# I2C_switch.net
KiCad netlist of a schematic drawn in Altium Designer
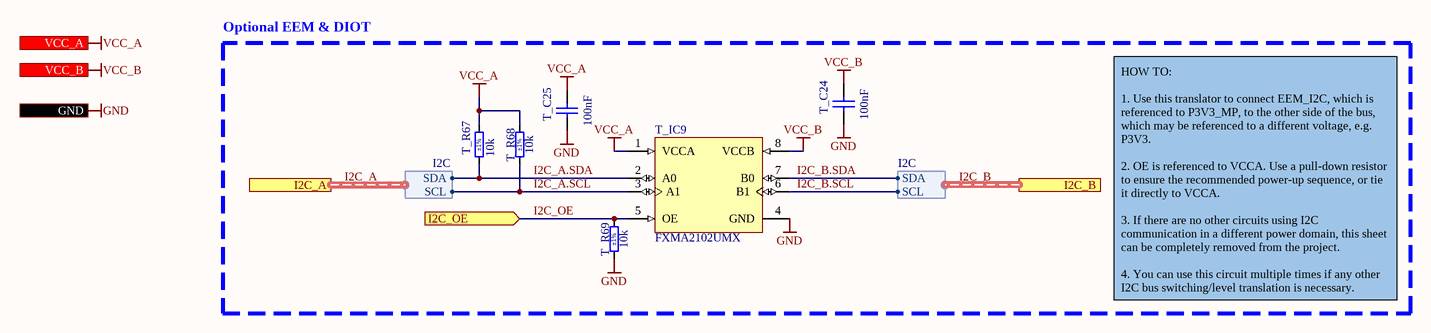
[diagram p0: I2C_switch.SchDoc]

(export (version "E")
  (design (tool "Eeschema 10.0.6"))
  (components
    (comp (ref "T_C24")
      (value "100nF")
      (footprint "CAPC1005X55N")
      (description "Non-polarised capacitor")
      (fields
        (field (name "PART NUMBER") "CC0402_100NF_16V_10%_X5R")
        (field (name "VOLTAGE") "16V")
        (field (name "AUTHOR") "CERN DEM JLC")
      )
      (libsource (lib "Capacitors") (part "Capacitor - non polarized"))
    )
    (comp (ref "T_C25")
      (value "100nF")
      (footprint "CAPC1005X55N")
      (description "Non-polarised capacitor")
      (fields
        (field (name "PART NUMBER") "CC0402_100NF_16V_10%_X5R")
        (field (name "VOLTAGE") "16V")
        (field (name "AUTHOR") "CERN DEM JLC")
      )
      (libsource (lib "Capacitors") (part "Capacitor - non polarized"))
    )
    (comp (ref "T_IC9")
      (value "FXMA2102UMX")
      (footprint "FXMA2102UMX")
      (description "Dual Supply 2-Bit Voltage Translator/Buffer/Repeater Isolator for I2C Applications")
      (fields (field (name "MANUFACTURER") "Onsemi"))
      (libsource (lib "TechnoSystem Workspace") (part "FXMA2102UMX"))
    )
    (comp (ref "T_R67")
      (value "10k")
      (footprint "RESC1005X40N")
      (description "Resistor - 1%")
      (fields
        (field (name "TOLERANCE") "±1%")
        (field (name "PART NUMBER") "R0402_10K_1%_0.0625W_100PPM")
        (field (name "POWER") "0.0625W")
        (field (name "AUTHOR") "CERN DEM JLC")
      )
      (libsource (lib "Resistors") (part "Resistor - 1%"))
    )
    (comp (ref "T_R68")
      (value "10k")
      (footprint "RESC1005X40N")
      (description "Resistor - 1%")
      (fields
        (field (name "TOLERANCE") "±1%")
        (field (name "PART NUMBER") "R0402_10K_1%_0.0625W_100PPM")
        (field (name "POWER") "0.0625W")
        (field (name "AUTHOR") "CERN DEM JLC")
      )
      (libsource (lib "Resistors") (part "Resistor - 1%"))
    )
    (comp (ref "T_R69")
      (value "10k")
      (footprint "RESC1005X40N")
      (description "Resistor - 1%")
      (fields
        (field (name "TOLERANCE") "±1%")
        (field (name "PART NUMBER") "R0402_10K_1%_0.0625W_100PPM")
        (field (name "POWER") "0.0625W")
        (field (name "AUTHOR") "CERN DEM JLC")
      )
      (libsource (lib "Resistors") (part "Resistor - 1%"))
    )
  )
  (nets
    (net (code "3") (name "/I2C_A.SCL") (class "Default")
      (node (ref "T_IC9") (pin "3") (pinfunction "A1_3") (pintype "bidirectional"))
      (node (ref "T_R68") (pin "1") (pinfunction "1_1") (pintype "passive"))
    )
    (net (code "4") (name "/I2C_A.SDA") (class "Default")
      (node (ref "T_IC9") (pin "2") (pinfunction "A0_2") (pintype "bidirectional"))
      (node (ref "T_R67") (pin "1") (pinfunction "1_1") (pintype "passive"))
    )
    (net (code "6") (name "/I2C_B.SCL") (class "Default")
      (node (ref "T_IC9") (pin "6") (pinfunction "B1_6") (pintype "bidirectional"))
    )
    (net (code "7") (name "/I2C_B.SDA") (class "Default")
      (node (ref "T_IC9") (pin "7") (pinfunction "B0_7") (pintype "bidirectional"))
    )
    (net (code "9") (name "/I2C_OE") (class "Default")
      (node (ref "T_IC9") (pin "5") (pinfunction "OE_5") (pintype "input"))
      (node (ref "T_R69") (pin "2") (pinfunction "2_2") (pintype "passive"))
    )
    (net (code "10") (name "GND") (class "Default")
      (node (ref "T_C24") (pin "1") (pinfunction "1_1") (pintype "passive"))
      (node (ref "T_C25") (pin "1") (pinfunction "1_1") (pintype "passive"))
      (node (ref "T_IC9") (pin "4") (pinfunction "GND_4") (pintype "power_in"))
      (node (ref "T_R69") (pin "1") (pinfunction "1_1") (pintype "passive"))
    )
    (net (code "11") (name "VCC_A") (class "Default")
      (node (ref "T_C25") (pin "2") (pinfunction "2_2") (pintype "passive"))
      (node (ref "T_IC9") (pin "1") (pinfunction "VCCA_1") (pintype "input"))
      (node (ref "T_R67") (pin "2") (pinfunction "2_2") (pintype "passive"))
      (node (ref "T_R68") (pin "2") (pinfunction "2_2") (pintype "passive"))
    )
    (net (code "12") (name "VCC_B") (class "Default")
      (node (ref "T_C24") (pin "2") (pinfunction "2_2") (pintype "passive"))
      (node (ref "T_IC9") (pin "8") (pinfunction "VCCB_8") (pintype "input"))
    )
  )
)
